# SparkFun_BabyBuck_Regulator_-_AP63203.net
KiCad netlist of a schematic drawn in EAGLE
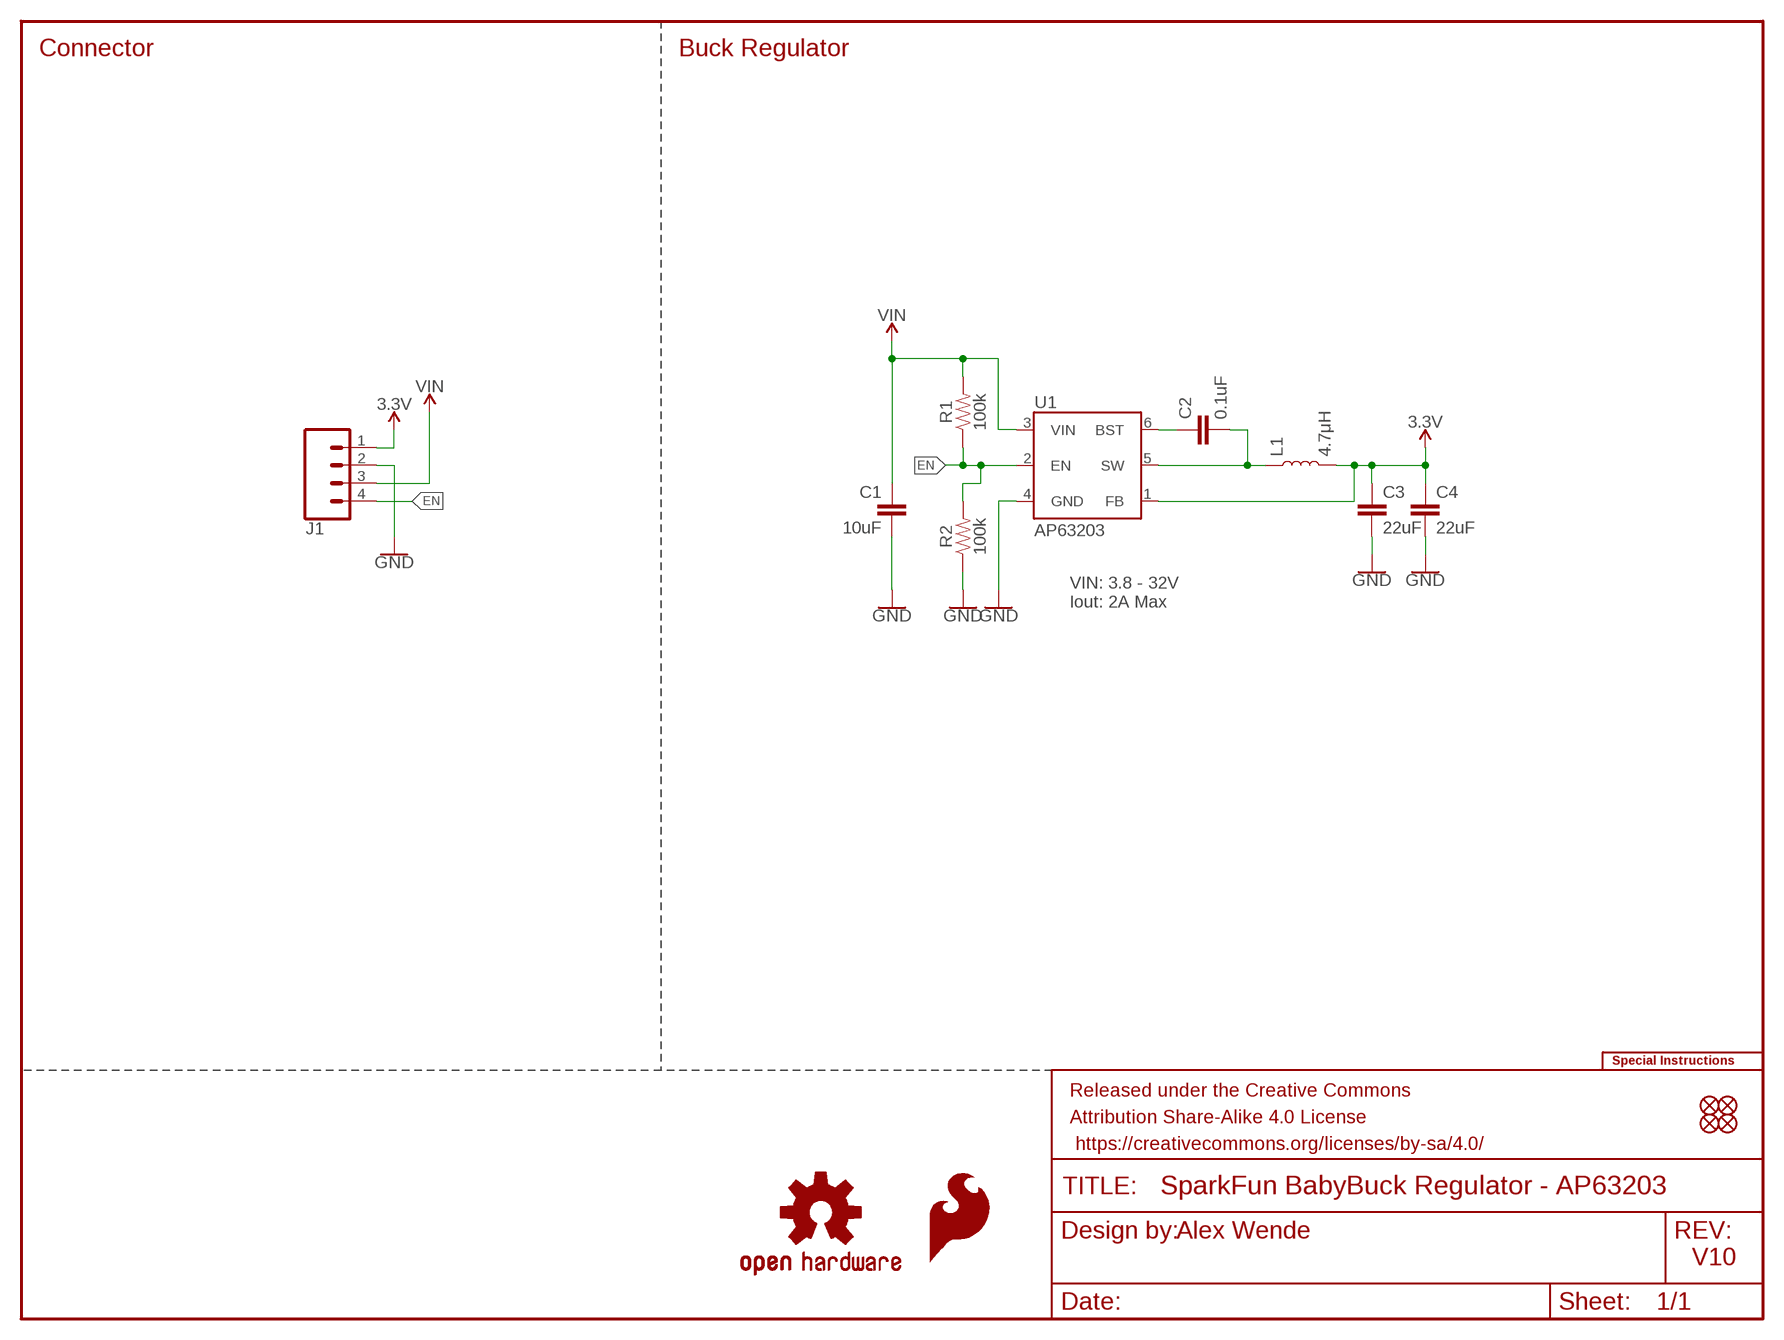
[diagram p0: schematic, sheet 1]

(export (version "E")
  (design (tool "Eeschema 10.0.6"))
  (components
    (comp (ref "C1")
      (value "10uF")
      (footprint "eagle-import:1210")
      (libsource (lib "eagle-import") (part "10UF-1210-50V-20%"))
    )
    (comp (ref "C2")
      (value "0.1uF")
      (footprint "eagle-import:0603")
      (libsource (lib "eagle-import") (part "0.1UF-0603-25V-5%"))
    )
    (comp (ref "C3")
      (value "22uF")
      (footprint "eagle-import:0603")
      (libsource (lib "eagle-import") (part "22UF-0603-6.3V-20%"))
    )
    (comp (ref "C4")
      (value "22uF")
      (footprint "eagle-import:0603")
      (libsource (lib "eagle-import") (part "22UF-0603-6.3V-20%"))
    )
    (comp (ref "FD1")
      (value "FIDUCIAL0.2MM")
      (footprint "eagle-import:FIDUCIAL-0.2MM")
      (libsource (lib "eagle-import") (part "FIDUCIAL0.2MM"))
    )
    (comp (ref "FD2")
      (value "FIDUCIAL0.2MM")
      (footprint "eagle-import:FIDUCIAL-0.2MM")
      (libsource (lib "eagle-import") (part "FIDUCIAL0.2MM"))
    )
    (comp (ref "FD3")
      (value "FIDUCIAL0.2MM")
      (footprint "eagle-import:FIDUCIAL-0.2MM")
      (libsource (lib "eagle-import") (part "FIDUCIAL0.2MM"))
    )
    (comp (ref "FD4")
      (value "FIDUCIAL0.2MM")
      (footprint "eagle-import:FIDUCIAL-0.2MM")
      (libsource (lib "eagle-import") (part "FIDUCIAL0.2MM"))
    )
    (comp (ref "FRAME1")
      (value "FRAME-LETTER")
      (footprint "eagle-import:CREATIVE_COMMONS")
      (libsource (lib "eagle-import") (part "FRAME-LETTER"))
    )
    (comp (ref "J1")
      (value "CONN_041X04_NO_SILK")
      (footprint "eagle-import:1X04_NO_SILK")
      (libsource (lib "eagle-import") (part "CONN_041X04_NO_SILK"))
    )
    (comp (ref "L1")
      (value "4.7μH")
      (footprint "eagle-import:INDUCTOR_4X4MM")
      (libsource (lib "eagle-import") (part "4.7μH_SHIELDED_INDUCTORNPIS_LS"))
    )
    (comp (ref "LOGO1")
      (value "SFE_LOGO_FLAME.1_INCH")
      (footprint "eagle-import:SFE_LOGO_FLAME_.1")
      (libsource (lib "eagle-import") (part "SFE_LOGO_FLAME.1_INCH"))
    )
    (comp (ref "LOGO2")
      (value "OSHW-LOGOS")
      (footprint "eagle-import:OSHW-LOGO-S")
      (libsource (lib "eagle-import") (part "OSHW-LOGOS"))
    )
    (comp (ref "LOGO3")
      (value "SPECIAL_INSTRUCTIONS-ORDERING")
      (footprint "eagle-import:ORDERING_INSTRUCTIONS")
      (libsource (lib "eagle-import") (part "SPECIAL_INSTRUCTIONS-ORDERING"))
    )
    (comp (ref "R1")
      (value "100k")
      (footprint "eagle-import:0603")
      (libsource (lib "eagle-import") (part "100KOHM-0603-1/10W-1%"))
    )
    (comp (ref "R2")
      (value "100k")
      (footprint "eagle-import:0603")
      (libsource (lib "eagle-import") (part "100KOHM-0603-1/10W-1%"))
    )
    (comp (ref "U1")
      (value "AP63203")
      (footprint "eagle-import:SOT23-6")
      (libsource (lib "eagle-import") (part "AP63203"))
    )
  )
  (nets
    (net (code "1") (name "3.3V") (class "Default")
      (node (ref "C3") (pin "1") (pinfunction "1_1") (pintype "passive"))
      (node (ref "C4") (pin "1") (pinfunction "1_1") (pintype "passive"))
      (node (ref "J1") (pin "1") (pinfunction "1_1") (pintype "passive"))
      (node (ref "L1") (pin "P$2") (pinfunction "2_P$2") (pintype "passive"))
      (node (ref "U1") (pin "1") (pinfunction "FB_1") (pintype "bidirectional"))
    )
    (net (code "2") (name "EN") (class "Default")
      (node (ref "J1") (pin "4") (pinfunction "4_4") (pintype "passive"))
      (node (ref "R1") (pin "1") (pinfunction "1_1") (pintype "passive"))
      (node (ref "R2") (pin "2") (pinfunction "2_2") (pintype "passive"))
      (node (ref "U1") (pin "2") (pinfunction "EN_2") (pintype "bidirectional"))
    )
    (net (code "3") (name "GND") (class "Default")
      (node (ref "C1") (pin "2") (pinfunction "2_2") (pintype "passive"))
      (node (ref "C3") (pin "2") (pinfunction "2_2") (pintype "passive"))
      (node (ref "C4") (pin "2") (pinfunction "2_2") (pintype "passive"))
      (node (ref "J1") (pin "2") (pinfunction "2_2") (pintype "passive"))
      (node (ref "R2") (pin "1") (pinfunction "1_1") (pintype "passive"))
      (node (ref "U1") (pin "4") (pinfunction "GND_4") (pintype "bidirectional"))
    )
    (net (code "4") (name "Net-(L1-1)") (class "Default")
      (node (ref "C2") (pin "2") (pinfunction "2_2") (pintype "passive"))
      (node (ref "L1") (pin "P$1") (pinfunction "1_P$1") (pintype "passive"))
      (node (ref "U1") (pin "5") (pinfunction "SW_5") (pintype "bidirectional"))
    )
    (net (code "5") (name "Net-(U1-BST)") (class "Default")
      (node (ref "C2") (pin "1") (pinfunction "1_1") (pintype "passive"))
      (node (ref "U1") (pin "6") (pinfunction "BST_6") (pintype "bidirectional"))
    )
    (net (code "6") (name "VIN") (class "Default")
      (node (ref "C1") (pin "1") (pinfunction "1_1") (pintype "passive"))
      (node (ref "J1") (pin "3") (pinfunction "3_3") (pintype "passive"))
      (node (ref "R1") (pin "2") (pinfunction "2_2") (pintype "passive"))
      (node (ref "U1") (pin "3") (pinfunction "VIN_3") (pintype "bidirectional"))
    )
  )
)
